# SimpleLDOConverter.net
KiCad netlist of a schematic drawn in Altium Designer
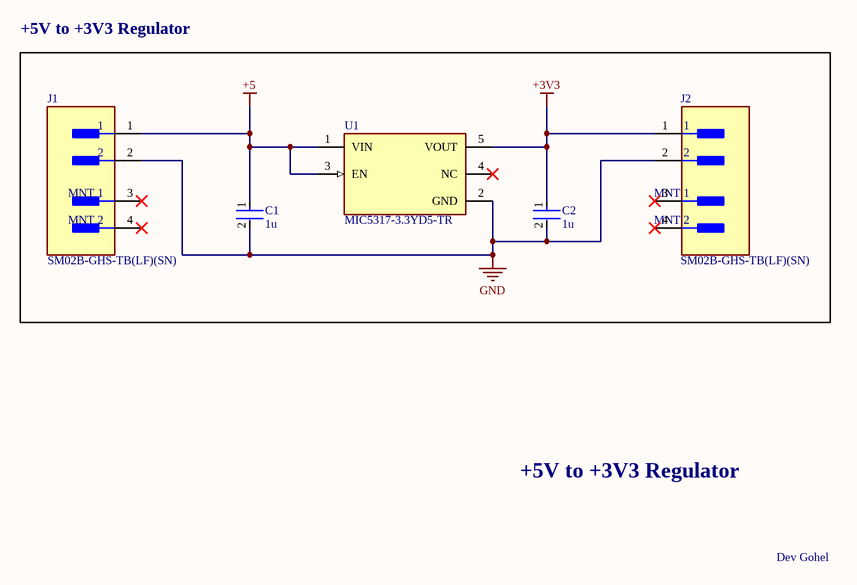
[diagram p0: SimpleLDOConverter.SchDoc]

(export (version "E")
  (design (tool "Eeschema 10.0.6"))
  (components
    (comp (ref "C1")
      (value "1u")
      (footprint "FP-CC0805-0_85-MFG")
      (description "CAP CER 1UF 10V X7R 0805")
      (fields
        (field (name "MANUFACTURER") "Yageo")
        (field (name "OCTOPART") "https://octopart.com/cc0805kkx7r6bb105-yageo-42522859")
      )
      (libsource (lib "Altium Content Vault") (part "11868f565c42a9108669ba33697ecf6"))
    )
    (comp (ref "C2")
      (value "1u")
      (footprint "FP-CC0805-0_85-MFG")
      (description "CAP CER 1UF 10V X7R 0805")
      (fields
        (field (name "MANUFACTURER") "Yageo")
        (field (name "OCTOPART") "https://octopart.com/cc0805kkx7r6bb105-yageo-42522859")
      )
      (libsource (lib "Altium Content Vault") (part "11868f565c42a9108669ba33697ecf6"))
    )
    (comp (ref "J1")
      (value "SM02B-GHS-TB(LF)(SN)")
      (footprint "FP-SM02B-GHS-TB_LF_SN-MFG")
      (description "CONN HEADER SMD R/A 2POS 1.25MM")
      (libsource (lib "Altium Content Vault") (part "56ec3178a87b3978bdc1b3682cd516a"))
    )
    (comp (ref "J2")
      (value "SM02B-GHS-TB(LF)(SN)")
      (footprint "FP-SM02B-GHS-TB_LF_SN-MFG")
      (description "CONN HEADER SMD R/A 2POS 1.25MM")
      (libsource (lib "") (part "56ec3178a87b3978bdc1b3682cd516a_1"))
    )
    (comp (ref "U1")
      (value "MIC5317-3.3YD5-TR")
      (footprint "FP-C04-1179-MFG")
      (description "MIC5317-3.3YD5-TR LDO Regulator Pos 3.3V 0.15A 5-Pin TSOT-23 T/R")
      (libsource (lib "Altium Content Vault") (part "ffa7970afa5bd4475d63c28c55078a9"))
    )
  )
  (nets
    (net (code "1") (name "+3V3") (class "Default")
      (node (ref "C2") (pin "1") (pinfunction "1_1") (pintype "passive"))
      (node (ref "J2") (pin "1") (pinfunction "1_1") (pintype "passive"))
      (node (ref "U1") (pin "5") (pinfunction "VOUT_5") (pintype "power_in"))
    )
    (net (code "2") (name "+5") (class "Default")
      (node (ref "C1") (pin "1") (pinfunction "1_1") (pintype "passive"))
      (node (ref "J1") (pin "1") (pinfunction "1_1") (pintype "passive"))
      (node (ref "U1") (pin "1") (pinfunction "VIN_1") (pintype "power_in"))
      (node (ref "U1") (pin "3") (pinfunction "EN_3") (pintype "input"))
    )
    (net (code "3") (name "GND") (class "Default")
      (node (ref "C1") (pin "2") (pinfunction "2_2") (pintype "passive"))
      (node (ref "C2") (pin "2") (pinfunction "2_2") (pintype "passive"))
      (node (ref "J1") (pin "2") (pinfunction "2_2") (pintype "passive"))
      (node (ref "J2") (pin "2") (pinfunction "2_2") (pintype "passive"))
      (node (ref "U1") (pin "2") (pinfunction "GND_2") (pintype "power_in"))
    )
    (net (code "4") (name "unconnected-(J1-MNT_1-Pad3)") (class "Default")
      (node (ref "J1") (pin "3") (pinfunction "MNT_1_3") (pintype "passive+no_connect"))
    )
    (net (code "5") (name "unconnected-(J1-MNT_2-Pad4)") (class "Default")
      (node (ref "J1") (pin "4") (pinfunction "MNT_2_4") (pintype "passive+no_connect"))
    )
    (net (code "6") (name "unconnected-(J2-MNT_1-Pad3)") (class "Default")
      (node (ref "J2") (pin "3") (pinfunction "MNT_1_3") (pintype "passive+no_connect"))
    )
    (net (code "7") (name "unconnected-(J2-MNT_2-Pad4)") (class "Default")
      (node (ref "J2") (pin "4") (pinfunction "MNT_2_4") (pintype "passive+no_connect"))
    )
    (net (code "8") (name "unconnected-(U1-NC-Pad4)") (class "Default")
      (node (ref "U1") (pin "4") (pinfunction "NC_4") (pintype "passive+no_connect"))
    )
  )
)
